# detector-discrete.net
KiCad netlist of a schematic drawn in EAGLE
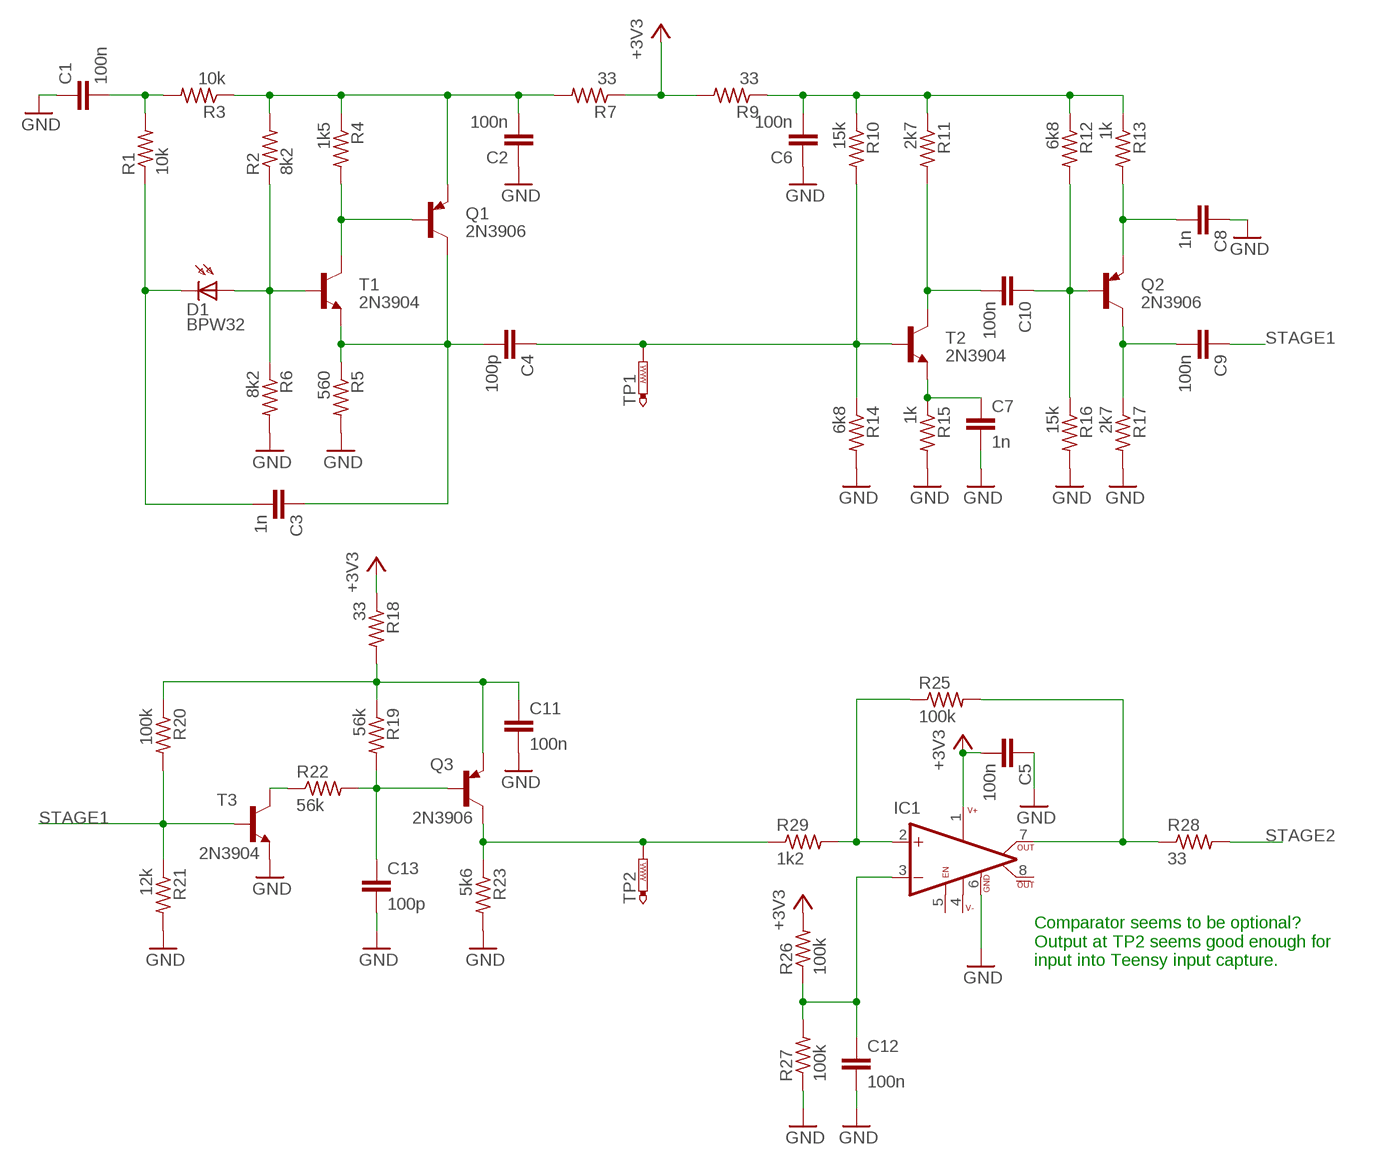
[diagram p0: schematic, sheet 1]

(export (version "E")
  (design (tool "Eeschema 10.0.6"))
  (components
    (comp (ref "C1")
      (value "100n")
      (footprint "eagle-import:C2.5-3")
      (libsource (lib "eagle-import") (part "C2,5-3"))
    )
    (comp (ref "C2")
      (value "100n")
      (footprint "eagle-import:C2.5-3")
      (libsource (lib "eagle-import") (part "C2,5-3"))
    )
    (comp (ref "C3")
      (value "1n")
      (footprint "eagle-import:C2.5-3")
      (libsource (lib "eagle-import") (part "C2,5-3"))
    )
    (comp (ref "C4")
      (value "100p")
      (footprint "eagle-import:C2.5-3")
      (libsource (lib "eagle-import") (part "C2,5-3"))
    )
    (comp (ref "C5")
      (value "100n")
      (footprint "eagle-import:C2.5-3")
      (libsource (lib "eagle-import") (part "C2,5-3"))
    )
    (comp (ref "C6")
      (value "100n")
      (footprint "eagle-import:C2.5-3")
      (libsource (lib "eagle-import") (part "C2,5-3"))
    )
    (comp (ref "C7")
      (value "1n")
      (footprint "eagle-import:C2.5-3")
      (libsource (lib "eagle-import") (part "C2,5-3"))
    )
    (comp (ref "C8")
      (value "1n")
      (footprint "eagle-import:C2.5-3")
      (libsource (lib "eagle-import") (part "C2,5-3"))
    )
    (comp (ref "C9")
      (value "100n")
      (footprint "eagle-import:C2.5-3")
      (libsource (lib "eagle-import") (part "C2,5-3"))
    )
    (comp (ref "C10")
      (value "100n")
      (footprint "eagle-import:C2.5-3")
      (libsource (lib "eagle-import") (part "C2,5-3"))
    )
    (comp (ref "C11")
      (value "100n")
      (footprint "eagle-import:C2.5-3")
      (libsource (lib "eagle-import") (part "C2,5-3"))
    )
    (comp (ref "C12")
      (value "100n")
      (footprint "eagle-import:C2.5-3")
      (libsource (lib "eagle-import") (part "C2,5-3"))
    )
    (comp (ref "C13")
      (value "100p")
      (footprint "eagle-import:C2.5-3")
      (libsource (lib "eagle-import") (part "C2,5-3"))
    )
    (comp (ref "D1")
      (value "BPW32")
      (footprint "eagle-import:BPW32")
      (libsource (lib "eagle-import") (part "BPW32"))
    )
    (comp (ref "IC1")
      (value "LT1016CN")
      (footprint "eagle-import:DIL08")
      (fields (field (name "MPN") "LT1016CN8"))
      (libsource (lib "eagle-import") (part "LT1016CN"))
    )
    (comp (ref "Q1")
      (value "2N3906")
      (footprint "eagle-import:TO92")
      (libsource (lib "eagle-import") (part "2N3906"))
    )
    (comp (ref "Q2")
      (value "2N3906")
      (footprint "eagle-import:TO92")
      (libsource (lib "eagle-import") (part "2N3906"))
    )
    (comp (ref "Q3")
      (value "2N3906")
      (footprint "eagle-import:TO92")
      (libsource (lib "eagle-import") (part "2N3906"))
    )
    (comp (ref "R1")
      (value "10k")
      (footprint "eagle-import:0204V")
      (libsource (lib "eagle-import") (part "R-US_0204/2V"))
    )
    (comp (ref "R2")
      (value "8k2")
      (footprint "eagle-import:0204V")
      (libsource (lib "eagle-import") (part "R-US_0204/2V"))
    )
    (comp (ref "R3")
      (value "10k")
      (footprint "eagle-import:0204V")
      (libsource (lib "eagle-import") (part "R-US_0204/2V"))
    )
    (comp (ref "R4")
      (value "1k5")
      (footprint "eagle-import:0204V")
      (libsource (lib "eagle-import") (part "R-US_0204/2V"))
    )
    (comp (ref "R5")
      (value "560")
      (footprint "eagle-import:0204V")
      (libsource (lib "eagle-import") (part "R-US_0204/2V"))
    )
    (comp (ref "R6")
      (value "8k2")
      (footprint "eagle-import:0204V")
      (libsource (lib "eagle-import") (part "R-US_0204/2V"))
    )
    (comp (ref "R7")
      (value "33")
      (footprint "eagle-import:0204V")
      (libsource (lib "eagle-import") (part "R-US_0204/2V"))
    )
    (comp (ref "R9")
      (value "33")
      (footprint "eagle-import:0204V")
      (libsource (lib "eagle-import") (part "R-US_0204/2V"))
    )
    (comp (ref "R10")
      (value "15k")
      (footprint "eagle-import:0204V")
      (libsource (lib "eagle-import") (part "R-US_0204/2V"))
    )
    (comp (ref "R11")
      (value "2k7")
      (footprint "eagle-import:0204V")
      (libsource (lib "eagle-import") (part "R-US_0204/2V"))
    )
    (comp (ref "R12")
      (value "6k8")
      (footprint "eagle-import:0204V")
      (libsource (lib "eagle-import") (part "R-US_0204/2V"))
    )
    (comp (ref "R13")
      (value "1k")
      (footprint "eagle-import:0204V")
      (libsource (lib "eagle-import") (part "R-US_0204/2V"))
    )
    (comp (ref "R14")
      (value "6k8")
      (footprint "eagle-import:0204V")
      (libsource (lib "eagle-import") (part "R-US_0204/2V"))
    )
    (comp (ref "R15")
      (value "1k")
      (footprint "eagle-import:0204V")
      (libsource (lib "eagle-import") (part "R-US_0204/2V"))
    )
    (comp (ref "R16")
      (value "15k")
      (footprint "eagle-import:0204V")
      (libsource (lib "eagle-import") (part "R-US_0204/2V"))
    )
    (comp (ref "R17")
      (value "2k7")
      (footprint "eagle-import:0204V")
      (libsource (lib "eagle-import") (part "R-US_0204/2V"))
    )
    (comp (ref "R18")
      (value "33")
      (footprint "eagle-import:0204V")
      (libsource (lib "eagle-import") (part "R-US_0204/2V"))
    )
    (comp (ref "R19")
      (value "56k")
      (footprint "eagle-import:0204V")
      (libsource (lib "eagle-import") (part "R-US_0204/2V"))
    )
    (comp (ref "R20")
      (value "100k")
      (footprint "eagle-import:0204V")
      (libsource (lib "eagle-import") (part "R-US_0204/2V"))
    )
    (comp (ref "R21")
      (value "12k")
      (footprint "eagle-import:0204V")
      (libsource (lib "eagle-import") (part "R-US_0204/2V"))
    )
    (comp (ref "R22")
      (value "56k")
      (footprint "eagle-import:0204V")
      (libsource (lib "eagle-import") (part "R-US_0204/2V"))
    )
    (comp (ref "R23")
      (value "5k6")
      (footprint "eagle-import:0204V")
      (libsource (lib "eagle-import") (part "R-US_0204/2V"))
    )
    (comp (ref "R25")
      (value "100k")
      (footprint "eagle-import:0204V")
      (libsource (lib "eagle-import") (part "R-US_0204/2V"))
    )
    (comp (ref "R26")
      (value "100k")
      (footprint "eagle-import:0204V")
      (libsource (lib "eagle-import") (part "R-US_0204/2V"))
    )
    (comp (ref "R27")
      (value "100k")
      (footprint "eagle-import:0204V")
      (libsource (lib "eagle-import") (part "R-US_0204/2V"))
    )
    (comp (ref "R28")
      (value "33")
      (footprint "eagle-import:0204V")
      (libsource (lib "eagle-import") (part "R-US_0204/2V"))
    )
    (comp (ref "R29")
      (value "1k2")
      (footprint "eagle-import:0204V")
      (libsource (lib "eagle-import") (part "R-US_0204/2V"))
    )
    (comp (ref "T1")
      (value "2N3904")
      (footprint "eagle-import:TO92")
      (libsource (lib "eagle-import") (part "2N3904"))
    )
    (comp (ref "T2")
      (value "2N3904")
      (footprint "eagle-import:TO92")
      (libsource (lib "eagle-import") (part "2N3904"))
    )
    (comp (ref "T3")
      (value "2N3904")
      (footprint "eagle-import:TO92")
      (libsource (lib "eagle-import") (part "2N3904"))
    )
    (comp (ref "TP1")
      (value "PTR1B1,27")
      (footprint "eagle-import:B1,27")
      (libsource (lib "eagle-import") (part "PTR1B1,27"))
    )
    (comp (ref "TP2")
      (value "PTR1B1,27")
      (footprint "eagle-import:B1,27")
      (libsource (lib "eagle-import") (part "PTR1B1,27"))
    )
  )
  (nets
    (net (code "1") (name "+3V3") (class "Default")
      (node (ref "C5") (pin "2") (pinfunction "2_2") (pintype "passive"))
      (node (ref "IC1") (pin "1") (pinfunction "V+_1") (pintype "power_in"))
      (node (ref "R18") (pin "1") (pinfunction "1_1") (pintype "passive"))
      (node (ref "R26") (pin "2") (pinfunction "2_2") (pintype "passive"))
      (node (ref "R7") (pin "1") (pinfunction "1_1") (pintype "passive"))
      (node (ref "R9") (pin "2") (pinfunction "2_2") (pintype "passive"))
    )
    (net (code "2") (name "/STAGE1") (class "Default")
      (node (ref "C9") (pin "1") (pinfunction "1_1") (pintype "passive"))
      (node (ref "R20") (pin "2") (pinfunction "2_2") (pintype "passive"))
      (node (ref "R21") (pin "1") (pinfunction "1_1") (pintype "passive"))
      (node (ref "T3") (pin "2") (pinfunction "B_2") (pintype "passive"))
    )
    (net (code "3") (name "/STAGE2") (class "Default")
      (node (ref "R28") (pin "2") (pinfunction "2_2") (pintype "passive"))
    )
    (net (code "4") (name "/V-") (class "Default")
      (node (ref "IC1") (pin "4") (pinfunction "V-_4") (pintype "power_in"))
    )
    (net (code "5") (name "GND") (class "Default")
      (node (ref "C1") (pin "1") (pinfunction "1_1") (pintype "passive"))
      (node (ref "C11") (pin "2") (pinfunction "2_2") (pintype "passive"))
      (node (ref "C12") (pin "2") (pinfunction "2_2") (pintype "passive"))
      (node (ref "C13") (pin "2") (pinfunction "2_2") (pintype "passive"))
      (node (ref "C2") (pin "1") (pinfunction "1_1") (pintype "passive"))
      (node (ref "C5") (pin "1") (pinfunction "1_1") (pintype "passive"))
      (node (ref "C6") (pin "1") (pinfunction "1_1") (pintype "passive"))
      (node (ref "C7") (pin "2") (pinfunction "2_2") (pintype "passive"))
      (node (ref "C8") (pin "1") (pinfunction "1_1") (pintype "passive"))
      (node (ref "IC1") (pin "6") (pinfunction "GND_6") (pintype "power_in"))
      (node (ref "R14") (pin "2") (pinfunction "2_2") (pintype "passive"))
      (node (ref "R15") (pin "2") (pinfunction "2_2") (pintype "passive"))
      (node (ref "R16") (pin "2") (pinfunction "2_2") (pintype "passive"))
      (node (ref "R17") (pin "2") (pinfunction "2_2") (pintype "passive"))
      (node (ref "R21") (pin "2") (pinfunction "2_2") (pintype "passive"))
      (node (ref "R23") (pin "2") (pinfunction "2_2") (pintype "passive"))
      (node (ref "R27") (pin "1") (pinfunction "1_1") (pintype "passive"))
      (node (ref "R5") (pin "2") (pinfunction "2_2") (pintype "passive"))
      (node (ref "R6") (pin "2") (pinfunction "2_2") (pintype "passive"))
      (node (ref "T3") (pin "3") (pinfunction "E_3") (pintype "passive"))
    )
    (net (code "6") (name "Net-(C1-Pad2)") (class "Default")
      (node (ref "C1") (pin "2") (pinfunction "2_2") (pintype "passive"))
      (node (ref "R1") (pin "2") (pinfunction "2_2") (pintype "passive"))
      (node (ref "R3") (pin "2") (pinfunction "2_2") (pintype "passive"))
    )
    (net (code "7") (name "Net-(C6-Pad2)") (class "Default")
      (node (ref "C6") (pin "2") (pinfunction "2_2") (pintype "passive"))
      (node (ref "R10") (pin "1") (pinfunction "1_1") (pintype "passive"))
      (node (ref "R11") (pin "1") (pinfunction "1_1") (pintype "passive"))
      (node (ref "R12") (pin "1") (pinfunction "1_1") (pintype "passive"))
      (node (ref "R13") (pin "1") (pinfunction "1_1") (pintype "passive"))
      (node (ref "R9") (pin "1") (pinfunction "1_1") (pintype "passive"))
    )
    (net (code "8") (name "Net-(D1-C)") (class "Default")
      (node (ref "C3") (pin "2") (pinfunction "2_2") (pintype "passive"))
      (node (ref "D1") (pin "K") (pinfunction "C_K") (pintype "passive"))
      (node (ref "R1") (pin "1") (pinfunction "1_1") (pintype "passive"))
    )
    (net (code "9") (name "Net-(IC1-+IN)") (class "Default")
      (node (ref "IC1") (pin "2") (pinfunction "+IN_2") (pintype "input"))
      (node (ref "R25") (pin "1") (pinfunction "1_1") (pintype "passive"))
      (node (ref "R29") (pin "2") (pinfunction "2_2") (pintype "passive"))
    )
    (net (code "10") (name "Net-(IC1--IN)") (class "Default")
      (node (ref "C12") (pin "1") (pinfunction "1_1") (pintype "passive"))
      (node (ref "IC1") (pin "3") (pinfunction "-IN_3") (pintype "input"))
      (node (ref "R26") (pin "1") (pinfunction "1_1") (pintype "passive"))
      (node (ref "R27") (pin "2") (pinfunction "2_2") (pintype "passive"))
    )
    (net (code "11") (name "Net-(IC1-OUT)") (class "Default")
      (node (ref "IC1") (pin "7") (pinfunction "OUT_7") (pintype "output"))
      (node (ref "R25") (pin "2") (pinfunction "2_2") (pintype "passive"))
      (node (ref "R28") (pin "1") (pinfunction "1_1") (pintype "passive"))
    )
    (net (code "12") (name "Net-(Q1-B)") (class "Default")
      (node (ref "Q1") (pin "2") (pinfunction "B_2") (pintype "passive"))
      (node (ref "R4") (pin "2") (pinfunction "2_2") (pintype "passive"))
      (node (ref "T1") (pin "1") (pinfunction "C_1") (pintype "passive"))
    )
    (net (code "13") (name "Net-(Q1-C)") (class "Default")
      (node (ref "C3") (pin "1") (pinfunction "1_1") (pintype "passive"))
      (node (ref "C4") (pin "2") (pinfunction "2_2") (pintype "passive"))
      (node (ref "Q1") (pin "1") (pinfunction "C_1") (pintype "passive"))
      (node (ref "R5") (pin "1") (pinfunction "1_1") (pintype "passive"))
      (node (ref "T1") (pin "3") (pinfunction "E_3") (pintype "passive"))
    )
    (net (code "14") (name "Net-(Q1-E)") (class "Default")
      (node (ref "C2") (pin "2") (pinfunction "2_2") (pintype "passive"))
      (node (ref "Q1") (pin "3") (pinfunction "E_3") (pintype "passive"))
      (node (ref "R2") (pin "2") (pinfunction "2_2") (pintype "passive"))
      (node (ref "R3") (pin "1") (pinfunction "1_1") (pintype "passive"))
      (node (ref "R4") (pin "1") (pinfunction "1_1") (pintype "passive"))
      (node (ref "R7") (pin "2") (pinfunction "2_2") (pintype "passive"))
    )
    (net (code "15") (name "Net-(Q2-B)") (class "Default")
      (node (ref "C10") (pin "1") (pinfunction "1_1") (pintype "passive"))
      (node (ref "Q2") (pin "2") (pinfunction "B_2") (pintype "passive"))
      (node (ref "R12") (pin "2") (pinfunction "2_2") (pintype "passive"))
      (node (ref "R16") (pin "1") (pinfunction "1_1") (pintype "passive"))
    )
    (net (code "16") (name "Net-(Q2-C)") (class "Default")
      (node (ref "C9") (pin "2") (pinfunction "2_2") (pintype "passive"))
      (node (ref "Q2") (pin "1") (pinfunction "C_1") (pintype "passive"))
      (node (ref "R17") (pin "1") (pinfunction "1_1") (pintype "passive"))
    )
    (net (code "17") (name "Net-(Q2-E)") (class "Default")
      (node (ref "C8") (pin "2") (pinfunction "2_2") (pintype "passive"))
      (node (ref "Q2") (pin "3") (pinfunction "E_3") (pintype "passive"))
      (node (ref "R13") (pin "2") (pinfunction "2_2") (pintype "passive"))
    )
    (net (code "18") (name "Net-(Q3-B)") (class "Default")
      (node (ref "C13") (pin "1") (pinfunction "1_1") (pintype "passive"))
      (node (ref "Q3") (pin "2") (pinfunction "B_2") (pintype "passive"))
      (node (ref "R19") (pin "2") (pinfunction "2_2") (pintype "passive"))
      (node (ref "R22") (pin "2") (pinfunction "2_2") (pintype "passive"))
    )
    (net (code "19") (name "Net-(Q3-C)") (class "Default")
      (node (ref "Q3") (pin "1") (pinfunction "C_1") (pintype "passive"))
      (node (ref "R23") (pin "1") (pinfunction "1_1") (pintype "passive"))
      (node (ref "R29") (pin "1") (pinfunction "1_1") (pintype "passive"))
      (node (ref "TP2") (pin "TP") (pinfunction "TP_TP") (pintype "input"))
    )
    (net (code "20") (name "Net-(Q3-E)") (class "Default")
      (node (ref "C11") (pin "1") (pinfunction "1_1") (pintype "passive"))
      (node (ref "Q3") (pin "3") (pinfunction "E_3") (pintype "passive"))
      (node (ref "R18") (pin "2") (pinfunction "2_2") (pintype "passive"))
      (node (ref "R19") (pin "1") (pinfunction "1_1") (pintype "passive"))
      (node (ref "R20") (pin "1") (pinfunction "1_1") (pintype "passive"))
    )
    (net (code "21") (name "Net-(T1-B)") (class "Default")
      (node (ref "D1") (pin "A") (pinfunction "A_A") (pintype "passive"))
      (node (ref "R2") (pin "1") (pinfunction "1_1") (pintype "passive"))
      (node (ref "R6") (pin "1") (pinfunction "1_1") (pintype "passive"))
      (node (ref "T1") (pin "2") (pinfunction "B_2") (pintype "passive"))
    )
    (net (code "22") (name "Net-(T2-B)") (class "Default")
      (node (ref "C4") (pin "1") (pinfunction "1_1") (pintype "passive"))
      (node (ref "R10") (pin "2") (pinfunction "2_2") (pintype "passive"))
      (node (ref "R14") (pin "1") (pinfunction "1_1") (pintype "passive"))
      (node (ref "T2") (pin "2") (pinfunction "B_2") (pintype "passive"))
      (node (ref "TP1") (pin "TP") (pinfunction "TP_TP") (pintype "input"))
    )
    (net (code "23") (name "Net-(T2-C)") (class "Default")
      (node (ref "C10") (pin "2") (pinfunction "2_2") (pintype "passive"))
      (node (ref "R11") (pin "2") (pinfunction "2_2") (pintype "passive"))
      (node (ref "T2") (pin "1") (pinfunction "C_1") (pintype "passive"))
    )
    (net (code "24") (name "Net-(T2-E)") (class "Default")
      (node (ref "C7") (pin "1") (pinfunction "1_1") (pintype "passive"))
      (node (ref "R15") (pin "1") (pinfunction "1_1") (pintype "passive"))
      (node (ref "T2") (pin "3") (pinfunction "E_3") (pintype "passive"))
    )
    (net (code "25") (name "Net-(T3-C)") (class "Default")
      (node (ref "R22") (pin "1") (pinfunction "1_1") (pintype "passive"))
      (node (ref "T3") (pin "1") (pinfunction "C_1") (pintype "passive"))
    )
    (net (code "26") (name "unconnected-(IC1-LA_EN-Pad5)") (class "Default")
      (node (ref "IC1") (pin "5") (pinfunction "LA_EN_5") (pintype "input"))
    )
    (net (code "27") (name "unconnected-(IC1-~{OUT}-Pad8)") (class "Default")
      (node (ref "IC1") (pin "8") (pinfunction "~{OUT}_8") (pintype "output"))
    )
  )
)
